# PowerSupplySMD.net
KiCad netlist of a schematic drawn in EAGLE
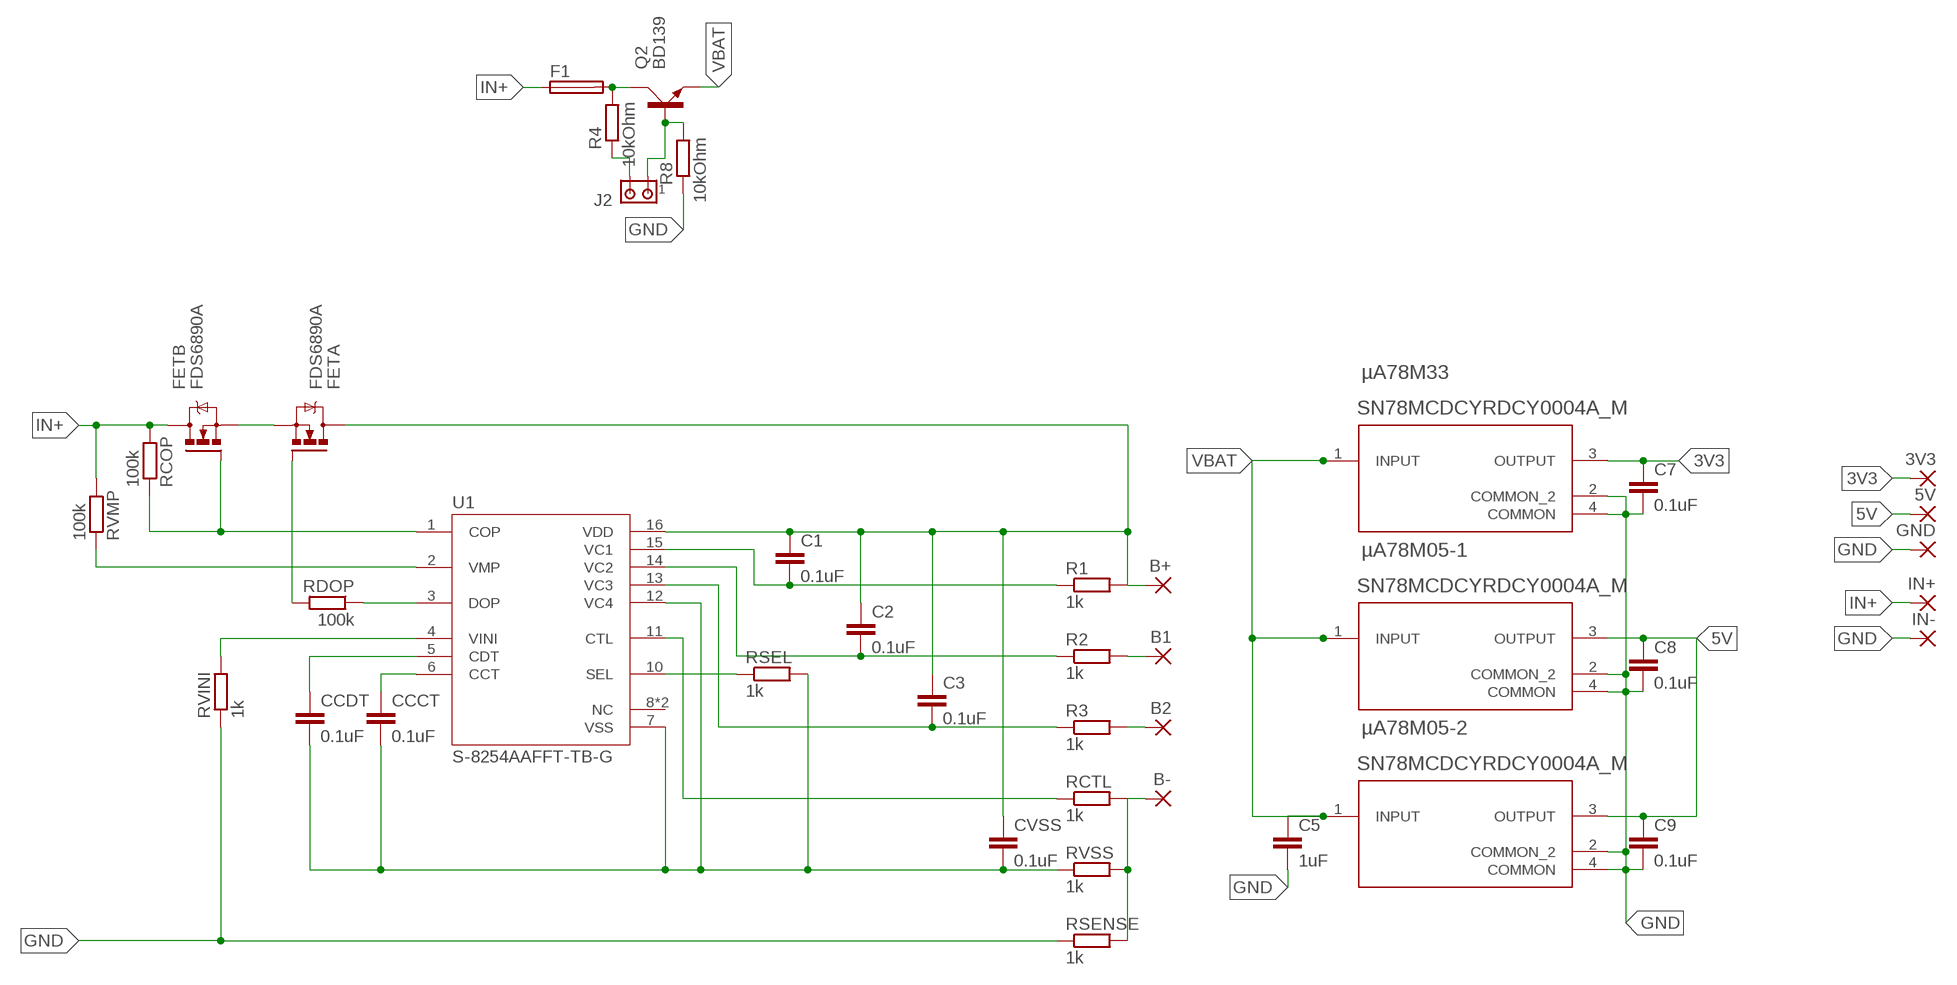
[diagram p0: schematic, sheet 1]

(export (version "E")
  (design (tool "Eeschema 10.0.6"))
  (components
    (comp (ref "3V3")
      (value "SMD5")
      (footprint "eagle-import:SMD2,54-5,08")
      (libsource (lib "eagle-import") (part "SMD5"))
    )
    (comp (ref "5V")
      (value "SMD5")
      (footprint "eagle-import:SMD2,54-5,08")
      (libsource (lib "eagle-import") (part "SMD5"))
    )
    (comp (ref "B+")
      (value "SMD5")
      (footprint "eagle-import:SMD2,54-5,08")
      (libsource (lib "eagle-import") (part "SMD5"))
    )
    (comp (ref "B-")
      (value "SMD5")
      (footprint "eagle-import:SMD2,54-5,08")
      (libsource (lib "eagle-import") (part "SMD5"))
    )
    (comp (ref "B1")
      (value "SMD5")
      (footprint "eagle-import:SMD2,54-5,08")
      (libsource (lib "eagle-import") (part "SMD5"))
    )
    (comp (ref "B2")
      (value "SMD5")
      (footprint "eagle-import:SMD2,54-5,08")
      (libsource (lib "eagle-import") (part "SMD5"))
    )
    (comp (ref "C1")
      (value "0.1uF")
      (footprint "eagle-import:C1206")
      (libsource (lib "eagle-import") (part "C-EUC1206"))
    )
    (comp (ref "C2")
      (value "0.1uF")
      (footprint "eagle-import:C1206")
      (libsource (lib "eagle-import") (part "C-EUC1206"))
    )
    (comp (ref "C3")
      (value "0.1uF")
      (footprint "eagle-import:C1206")
      (libsource (lib "eagle-import") (part "C-EUC1206"))
    )
    (comp (ref "C5")
      (value "1uF")
      (footprint "eagle-import:C1206")
      (libsource (lib "eagle-import") (part "C-EUC1206"))
    )
    (comp (ref "C7")
      (value "0.1uF")
      (footprint "eagle-import:C1206")
      (libsource (lib "eagle-import") (part "C-EUC1206"))
    )
    (comp (ref "C8")
      (value "0.1uF")
      (footprint "eagle-import:C1206")
      (libsource (lib "eagle-import") (part "C-EUC1206"))
    )
    (comp (ref "C9")
      (value "0.1uF")
      (footprint "eagle-import:C1206")
      (libsource (lib "eagle-import") (part "C-EUC1206"))
    )
    (comp (ref "CCCT")
      (value "0.1uF")
      (footprint "eagle-import:C1206")
      (libsource (lib "eagle-import") (part "C-EUC1206"))
    )
    (comp (ref "CCDT")
      (value "0.1uF")
      (footprint "eagle-import:C1206")
      (libsource (lib "eagle-import") (part "C-EUC1206"))
    )
    (comp (ref "CVSS")
      (value "0.1uF")
      (footprint "eagle-import:C1206")
      (libsource (lib "eagle-import") (part "C-EUC1206"))
    )
    (comp (ref "F1")
      (value "FUSEBLANK_5X20MM")
      (footprint "eagle-import:FUSE_HOLDER_5X20MM")
      (libsource (lib "eagle-import") (part "FUSEBLANK_5X20MM"))
    )
    (comp (ref "FET")
      (value "FDS6890A")
      (footprint "eagle-import:M08A")
      (libsource (lib "eagle-import") (part "FDS6890A"))
    )
    (comp (ref "GND")
      (value "SMD5")
      (footprint "eagle-import:SMD2,54-5,08")
      (libsource (lib "eagle-import") (part "SMD5"))
    )
    (comp (ref "IN+")
      (value "SMD5")
      (footprint "eagle-import:SMD2,54-5,08")
      (libsource (lib "eagle-import") (part "SMD5"))
    )
    (comp (ref "IN-")
      (value "SMD5")
      (footprint "eagle-import:SMD2,54-5,08")
      (libsource (lib "eagle-import") (part "SMD5"))
    )
    (comp (ref "J2")
      (value "MTA02-100")
      (footprint "eagle-import:10X02MTA")
      (libsource (lib "eagle-import") (part "MTA02-100"))
    )
    (comp (ref "Q2")
      (value "BD139")
      (footprint "eagle-import:TO126AV")
      (libsource (lib "eagle-import") (part "BD139"))
    )
    (comp (ref "R1")
      (value "1k")
      (footprint "eagle-import:R1206")
      (libsource (lib "eagle-import") (part "R-EU_R1206"))
    )
    (comp (ref "R2")
      (value "1k")
      (footprint "eagle-import:R1206")
      (libsource (lib "eagle-import") (part "R-EU_R1206"))
    )
    (comp (ref "R3")
      (value "1k")
      (footprint "eagle-import:R1206")
      (libsource (lib "eagle-import") (part "R-EU_R1206"))
    )
    (comp (ref "R4")
      (value "10kOhm")
      (footprint "eagle-import:R1206")
      (libsource (lib "eagle-import") (part "R-EU_R1206"))
    )
    (comp (ref "R8")
      (value "10kOhm")
      (footprint "eagle-import:R1206")
      (libsource (lib "eagle-import") (part "R-EU_R1206"))
    )
    (comp (ref "RCOP")
      (value "100k")
      (footprint "eagle-import:R1206")
      (libsource (lib "eagle-import") (part "R-EU_R1206"))
    )
    (comp (ref "RCTL")
      (value "1k")
      (footprint "eagle-import:R1206")
      (libsource (lib "eagle-import") (part "R-EU_R1206"))
    )
    (comp (ref "RDOP")
      (value "100k")
      (footprint "eagle-import:R1206")
      (libsource (lib "eagle-import") (part "R-EU_R1206"))
    )
    (comp (ref "RSEL")
      (value "1k")
      (footprint "eagle-import:R1206")
      (libsource (lib "eagle-import") (part "R-EU_R1206"))
    )
    (comp (ref "RSENSE")
      (value "1k")
      (footprint "eagle-import:R1206")
      (libsource (lib "eagle-import") (part "R-EU_R1206"))
    )
    (comp (ref "RVINI")
      (value "1k")
      (footprint "eagle-import:R1206")
      (libsource (lib "eagle-import") (part "R-EU_R1206"))
    )
    (comp (ref "RVMP")
      (value "100k")
      (footprint "eagle-import:R1206")
      (libsource (lib "eagle-import") (part "R-EU_R1206"))
    )
    (comp (ref "RVSS")
      (value "1k")
      (footprint "eagle-import:R1206")
      (libsource (lib "eagle-import") (part "R-EU_R1206"))
    )
    (comp (ref "U1")
      (value "S-8254AAFFT-TB-G")
      (footprint "eagle-import:SOP65P640X110-16N")
      (fields (field (name "MF") "Seiko"))
      (libsource (lib "eagle-import") (part "S-8254AAFFT-TB-G"))
    )
    (comp (ref "µA78M05-1")
      (value "SN78MCDCYRDCY0004A_M")
      (footprint "eagle-import:DCY0004A_M")
      (fields
        (field (name "MANUFACTURER_PART_NUMBER") "SN78MCDCYR")
        (field (name "COPYRIGHT") "Copyright (C) 2023 Ultra Librarian. All rights reserved.")
      )
      (libsource (lib "eagle-import") (part "SN78MCDCYRDCY0004A_M"))
    )
    (comp (ref "µA78M05-2")
      (value "SN78MCDCYRDCY0004A_M")
      (footprint "eagle-import:DCY0004A_M")
      (fields
        (field (name "MANUFACTURER_PART_NUMBER") "SN78MCDCYR")
        (field (name "COPYRIGHT") "Copyright (C) 2023 Ultra Librarian. All rights reserved.")
      )
      (libsource (lib "eagle-import") (part "SN78MCDCYRDCY0004A_M"))
    )
    (comp (ref "µA78M33")
      (value "SN78MCDCYRDCY0004A_M")
      (footprint "eagle-import:DCY0004A_M")
      (fields
        (field (name "MANUFACTURER_PART_NUMBER") "SN78MCDCYR")
        (field (name "COPYRIGHT") "Copyright (C) 2023 Ultra Librarian. All rights reserved.")
      )
      (libsource (lib "eagle-import") (part "SN78MCDCYRDCY0004A_M"))
    )
  )
  (nets
    (net (code "1") (name "3V3") (class "Default")
      (node (ref "3V3") (pin "1") (pinfunction "P_1") (pintype "passive"))
      (node (ref "C7") (pin "1") (pinfunction "1_1") (pintype "passive"))
      (node (ref "µA78M33") (pin "3") (pinfunction "OUTPUT_3") (pintype "power_in"))
    )
    (net (code "2") (name "5V") (class "Default")
      (node (ref "5V") (pin "1") (pinfunction "P_1") (pintype "passive"))
      (node (ref "C8") (pin "1") (pinfunction "1_1") (pintype "passive"))
      (node (ref "C9") (pin "1") (pinfunction "1_1") (pintype "passive"))
      (node (ref "µA78M05-1") (pin "3") (pinfunction "OUTPUT_3") (pintype "power_in"))
      (node (ref "µA78M05-2") (pin "3") (pinfunction "OUTPUT_3") (pintype "power_in"))
    )
    (net (code "3") (name "GND") (class "Default")
      (node (ref "C5") (pin "2") (pinfunction "2_2") (pintype "passive"))
      (node (ref "C7") (pin "2") (pinfunction "2_2") (pintype "passive"))
      (node (ref "C8") (pin "2") (pinfunction "2_2") (pintype "passive"))
      (node (ref "C9") (pin "2") (pinfunction "2_2") (pintype "passive"))
      (node (ref "GND") (pin "1") (pinfunction "P_1") (pintype "passive"))
      (node (ref "IN-") (pin "1") (pinfunction "P_1") (pintype "passive"))
      (node (ref "R8") (pin "1") (pinfunction "1_1") (pintype "passive"))
      (node (ref "RSENSE") (pin "1") (pinfunction "1_1") (pintype "passive"))
      (node (ref "RVINI") (pin "1") (pinfunction "1_1") (pintype "passive"))
      (node (ref "µA78M05-1") (pin "2") (pinfunction "COMMON_2_2") (pintype "power_in"))
      (node (ref "µA78M05-1") (pin "4") (pinfunction "COMMON_4") (pintype "power_in"))
      (node (ref "µA78M05-2") (pin "2") (pinfunction "COMMON_2_2") (pintype "power_in"))
      (node (ref "µA78M05-2") (pin "4") (pinfunction "COMMON_4") (pintype "power_in"))
      (node (ref "µA78M33") (pin "2") (pinfunction "COMMON_2_2") (pintype "power_in"))
      (node (ref "µA78M33") (pin "4") (pinfunction "COMMON_4") (pintype "power_in"))
    )
    (net (code "4") (name "IN+") (class "Default")
      (node (ref "F1") (pin "1") (pinfunction "1_1") (pintype "passive"))
      (node (ref "FET") (pin "5") (pinfunction "D_5") (pintype "passive"))
      (node (ref "FET") (pin "6") (pinfunction "D_6") (pintype "passive"))
      (node (ref "IN+") (pin "1") (pinfunction "P_1") (pintype "passive"))
      (node (ref "RCOP") (pin "2") (pinfunction "2_2") (pintype "passive"))
      (node (ref "RVMP") (pin "2") (pinfunction "2_2") (pintype "passive"))
    )
    (net (code "5") (name "Net-(B+-P)") (class "Default")
      (node (ref "B+") (pin "1") (pinfunction "P_1") (pintype "passive"))
      (node (ref "C1") (pin "1") (pinfunction "1_1") (pintype "passive"))
      (node (ref "C2") (pin "1") (pinfunction "1_1") (pintype "passive"))
      (node (ref "C3") (pin "1") (pinfunction "1_1") (pintype "passive"))
      (node (ref "CVSS") (pin "1") (pinfunction "1_1") (pintype "passive"))
      (node (ref "FET") (pin "7") (pinfunction "D_7") (pintype "passive"))
      (node (ref "FET") (pin "8") (pinfunction "D_8") (pintype "passive"))
      (node (ref "R1") (pin "2") (pinfunction "2_2") (pintype "passive"))
      (node (ref "U1") (pin "16") (pinfunction "VDD_16") (pintype "power_in"))
    )
    (net (code "6") (name "Net-(B--P)") (class "Default")
      (node (ref "B-") (pin "1") (pinfunction "P_1") (pintype "passive"))
      (node (ref "RCTL") (pin "2") (pinfunction "2_2") (pintype "passive"))
      (node (ref "RSENSE") (pin "2") (pinfunction "2_2") (pintype "passive"))
      (node (ref "RVSS") (pin "2") (pinfunction "2_2") (pintype "passive"))
    )
    (net (code "7") (name "Net-(B1-P)") (class "Default")
      (node (ref "B1") (pin "1") (pinfunction "P_1") (pintype "passive"))
      (node (ref "R2") (pin "2") (pinfunction "2_2") (pintype "passive"))
    )
    (net (code "8") (name "Net-(B2-P)") (class "Default")
      (node (ref "B2") (pin "1") (pinfunction "P_1") (pintype "passive"))
      (node (ref "R3") (pin "2") (pinfunction "2_2") (pintype "passive"))
    )
    (net (code "9") (name "Net-(F1-Pad2)") (class "Default")
      (node (ref "F1") (pin "2") (pinfunction "2_2") (pintype "passive"))
      (node (ref "Q2") (pin "C") (pinfunction "C_C") (pintype "passive"))
      (node (ref "R4") (pin "2") (pinfunction "2_2") (pintype "passive"))
    )
    (net (code "10") (name "Net-(FETA-G)") (class "Default")
      (node (ref "FET") (pin "2") (pinfunction "G_2") (pintype "passive"))
      (node (ref "RDOP") (pin "2") (pinfunction "2_2") (pintype "passive"))
    )
    (net (code "11") (name "Net-(FETA-S)") (class "Default")
      (node (ref "FET") (pin "1") (pinfunction "S_1") (pintype "passive"))
      (node (ref "FET") (pin "3") (pinfunction "S_3") (pintype "passive"))
    )
    (net (code "12") (name "Net-(FETB-G)") (class "Default")
      (node (ref "FET") (pin "4") (pinfunction "G_4") (pintype "passive"))
      (node (ref "RCOP") (pin "1") (pinfunction "1_1") (pintype "passive"))
      (node (ref "U1") (pin "1") (pinfunction "COP_1") (pintype "output"))
    )
    (net (code "13") (name "Net-(J2-Pad1)") (class "Default")
      (node (ref "J2") (pin "1") (pinfunction "1_1") (pintype "passive"))
      (node (ref "Q2") (pin "B") (pinfunction "B_B") (pintype "passive"))
      (node (ref "R8") (pin "2") (pinfunction "2_2") (pintype "passive"))
    )
    (net (code "14") (name "Net-(J2-Pad2)") (class "Default")
      (node (ref "J2") (pin "2") (pinfunction "2_2") (pintype "passive"))
      (node (ref "R4") (pin "1") (pinfunction "1_1") (pintype "passive"))
    )
    (net (code "15") (name "Net-(U1-CCT)") (class "Default")
      (node (ref "CCCT") (pin "1") (pinfunction "1_1") (pintype "passive"))
      (node (ref "U1") (pin "6") (pinfunction "CCT_6") (pintype "passive"))
    )
    (net (code "16") (name "Net-(U1-CDT)") (class "Default")
      (node (ref "CCDT") (pin "1") (pinfunction "1_1") (pintype "passive"))
      (node (ref "U1") (pin "5") (pinfunction "CDT_5") (pintype "passive"))
    )
    (net (code "17") (name "Net-(U1-CTL)") (class "Default")
      (node (ref "RCTL") (pin "1") (pinfunction "1_1") (pintype "passive"))
      (node (ref "U1") (pin "11") (pinfunction "CTL_11") (pintype "input"))
    )
    (net (code "18") (name "Net-(U1-DOP)") (class "Default")
      (node (ref "RDOP") (pin "1") (pinfunction "1_1") (pintype "passive"))
      (node (ref "U1") (pin "3") (pinfunction "DOP_3") (pintype "output"))
    )
    (net (code "19") (name "Net-(U1-SEL)") (class "Default")
      (node (ref "RSEL") (pin "1") (pinfunction "1_1") (pintype "passive"))
      (node (ref "U1") (pin "10") (pinfunction "SEL_10") (pintype "passive"))
    )
    (net (code "20") (name "Net-(U1-VC1)") (class "Default")
      (node (ref "C1") (pin "2") (pinfunction "2_2") (pintype "passive"))
      (node (ref "R1") (pin "1") (pinfunction "1_1") (pintype "passive"))
      (node (ref "U1") (pin "15") (pinfunction "VC1_15") (pintype "power_in"))
    )
    (net (code "21") (name "Net-(U1-VC2)") (class "Default")
      (node (ref "C2") (pin "2") (pinfunction "2_2") (pintype "passive"))
      (node (ref "R2") (pin "1") (pinfunction "1_1") (pintype "passive"))
      (node (ref "U1") (pin "14") (pinfunction "VC2_14") (pintype "power_in"))
    )
    (net (code "22") (name "Net-(U1-VC3)") (class "Default")
      (node (ref "C3") (pin "2") (pinfunction "2_2") (pintype "passive"))
      (node (ref "R3") (pin "1") (pinfunction "1_1") (pintype "passive"))
      (node (ref "U1") (pin "13") (pinfunction "VC3_13") (pintype "power_in"))
    )
    (net (code "23") (name "Net-(U1-VC4)") (class "Default")
      (node (ref "CCCT") (pin "2") (pinfunction "2_2") (pintype "passive"))
      (node (ref "CCDT") (pin "2") (pinfunction "2_2") (pintype "passive"))
      (node (ref "CVSS") (pin "2") (pinfunction "2_2") (pintype "passive"))
      (node (ref "RSEL") (pin "2") (pinfunction "2_2") (pintype "passive"))
      (node (ref "RVSS") (pin "1") (pinfunction "1_1") (pintype "passive"))
      (node (ref "U1") (pin "12") (pinfunction "VC4_12") (pintype "power_in"))
      (node (ref "U1") (pin "7") (pinfunction "VSS_7") (pintype "power_in"))
    )
    (net (code "24") (name "Net-(U1-VINI)") (class "Default")
      (node (ref "RVINI") (pin "2") (pinfunction "2_2") (pintype "passive"))
      (node (ref "U1") (pin "4") (pinfunction "VINI_4") (pintype "passive"))
    )
    (net (code "25") (name "Net-(U1-VMP)") (class "Default")
      (node (ref "RVMP") (pin "1") (pinfunction "1_1") (pintype "passive"))
      (node (ref "U1") (pin "2") (pinfunction "VMP_2") (pintype "passive"))
    )
    (net (code "26") (name "VBAT") (class "Default")
      (node (ref "C5") (pin "1") (pinfunction "1_1") (pintype "passive"))
      (node (ref "Q2") (pin "E") (pinfunction "E_E") (pintype "passive"))
      (node (ref "µA78M05-1") (pin "1") (pinfunction "INPUT_1") (pintype "power_in"))
      (node (ref "µA78M05-2") (pin "1") (pinfunction "INPUT_1") (pintype "power_in"))
      (node (ref "µA78M33") (pin "1") (pinfunction "INPUT_1") (pintype "power_in"))
    )
    (net (code "27") (name "unconnected-(U1-NC-Pad8)") (class "Default")
      (node (ref "U1") (pin "8") (pinfunction "NC_8") (pintype "no_connect"))
    )
    (net (code "28") (name "unconnected-(U1-NC-Pad9)") (class "Default")
      (node (ref "U1") (pin "9") (pinfunction "NC_9") (pintype "no_connect"))
    )
  )
)
